# F405_MCU.net
KiCad netlist of a schematic drawn in Altium Designer
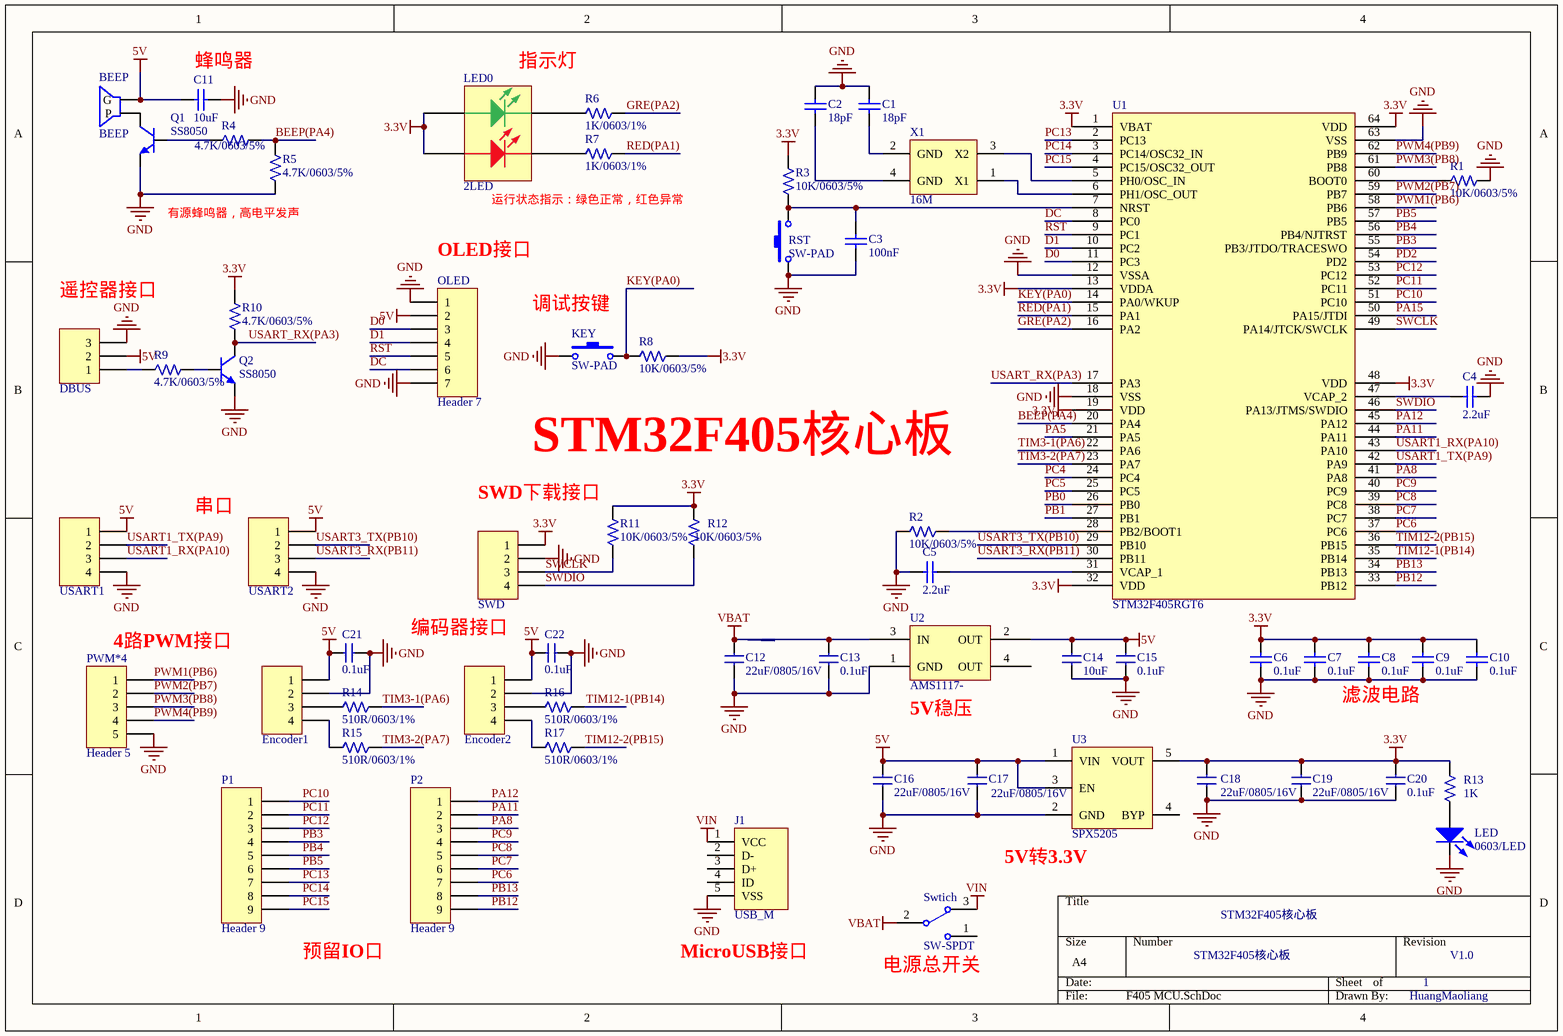
[diagram p0: F405 MCU.SchDoc]

(export (version "E")
  (design (tool "Eeschema 10.0.6"))
  (components
    (comp (ref "BEEP") (value "BEEP") (footprint "BELL-5") (libsource (lib "WARSHIP_SCH") (part "BEEP")))
    (comp (ref "C1")
      (value "18pF")
      (footprint "CAP-0603")
      (description "无极性电容")
      (fields (field (name "PUBLISHER") "Altium Limited"))
      (libsource (lib "My_Library") (part "Cap"))
    )
    (comp (ref "C2")
      (value "18pF")
      (footprint "CAP-0603")
      (description "无极性电容")
      (fields (field (name "PUBLISHER") "Altium Limited"))
      (libsource (lib "My_Library") (part "Cap"))
    )
    (comp (ref "C3")
      (value "100nF")
      (footprint "CAP-0603")
      (description "无极性电容")
      (fields (field (name "PUBLISHER") "Altium Limited"))
      (libsource (lib "My_Library") (part "Cap"))
    )
    (comp (ref "C4")
      (value "2.2uF")
      (footprint "CAP-0603")
      (description "无极性电容")
      (fields (field (name "PUBLISHER") "Altium Limited"))
      (libsource (lib "My_Library") (part "Cap"))
    )
    (comp (ref "C5")
      (value "2.2uF")
      (footprint "CAP-0603")
      (description "无极性电容")
      (fields (field (name "PUBLISHER") "Altium Limited"))
      (libsource (lib "My_Library") (part "Cap"))
    )
    (comp (ref "C6")
      (value "0.1uF")
      (footprint "CAP-0603")
      (description "无极性电容")
      (fields (field (name "PUBLISHER") "Altium Limited"))
      (libsource (lib "My_Library") (part "Cap"))
    )
    (comp (ref "C7")
      (value "0.1uF")
      (footprint "CAP-0603")
      (description "无极性电容")
      (fields (field (name "PUBLISHER") "Altium Limited"))
      (libsource (lib "My_Library") (part "Cap"))
    )
    (comp (ref "C8")
      (value "0.1uF")
      (footprint "CAP-0603")
      (description "无极性电容")
      (fields (field (name "PUBLISHER") "Altium Limited"))
      (libsource (lib "My_Library") (part "Cap"))
    )
    (comp (ref "C9")
      (value "0.1uF")
      (footprint "CAP-0603")
      (description "无极性电容")
      (fields (field (name "PUBLISHER") "Altium Limited"))
      (libsource (lib "My_Library") (part "Cap"))
    )
    (comp (ref "C10")
      (value "0.1uF")
      (footprint "CAP-0603")
      (description "无极性电容")
      (fields (field (name "PUBLISHER") "Altium Limited"))
      (libsource (lib "My_Library") (part "Cap"))
    )
    (comp (ref "C11")
      (value "10uF")
      (footprint "CAP-0603")
      (description "无极性电容")
      (fields (field (name "PUBLISHER") "Altium Limited"))
      (libsource (lib "My_Library") (part "Cap"))
    )
    (comp (ref "C12")
      (value "22uF/0805/16V")
      (footprint "0805")
      (libsource (lib "main control") (part "CAP/0805"))
    )
    (comp (ref "C13") (value "0.1uF") (footprint "0603") (libsource (lib "main control") (part "CAP/0603")))
    (comp (ref "C14") (value "10uF") (footprint "0603") (libsource (lib "main control") (part "CAP/0603")))
    (comp (ref "C15") (value "0.1uF") (footprint "0603") (libsource (lib "main control") (part "CAP/0603")))
    (comp (ref "C16")
      (value "22uF/0805/16V")
      (footprint "0805")
      (libsource (lib "main control") (part "CAP/0805"))
    )
    (comp (ref "C17")
      (value "22uF/0805/16V")
      (footprint "0805")
      (libsource (lib "main control") (part "CAP/0805"))
    )
    (comp (ref "C18")
      (value "22uF/0805/16V")
      (footprint "0805")
      (libsource (lib "main control") (part "CAP/0805"))
    )
    (comp (ref "C19")
      (value "22uF/0805/16V")
      (footprint "0805")
      (libsource (lib "main control") (part "CAP/0805"))
    )
    (comp (ref "C20") (value "0.1uF") (footprint "0603") (libsource (lib "main control") (part "CAP/0603")))
    (comp (ref "C21") (value "0.1uF") (footprint "0603") (libsource (lib "main control") (part "CAP/0603")))
    (comp (ref "C22") (value "0.1uF") (footprint "0603") (libsource (lib "main control") (part "CAP/0603")))
    (comp (ref "DBUS")
      (value "Header 3")
      (footprint "HDR3X1_A")
      (description "接插件")
      (fields (field (name "PUBLISHER") "Altium Limited"))
      (libsource (lib "Fszhang") (part "Header 3"))
    )
    (comp (ref "Encoder1")
      (value "Header 4")
      (footprint "HDR4X1_A")
      (description "接插件")
      (fields (field (name "PUBLISHER") "Altium Limited"))
      (libsource (lib "Fszhang") (part "Header 4"))
    )
    (comp (ref "Encoder2")
      (value "Header 4")
      (footprint "HDR4X1_A")
      (description "接插件")
      (fields (field (name "PUBLISHER") "Altium Limited"))
      (libsource (lib "Fszhang") (part "Header 4"))
    )
    (comp (ref "J1")
      (value "USB_M")
      (footprint "USB-MICRO")
      (description "MicroUSB接口")
      (libsource (lib "My_Library") (part "USB_M"))
    )
    (comp (ref "KEY")
      (value "SW-PAD")
      (footprint "SW_PAD1")
      (description "微动开关")
      (fields (field (name "PUBLISHER") "Altium Limited"))
      (libsource (lib "My_Library") (part "SW-PAD"))
    )
    (comp (ref "LED")
      (value "0603/LED")
      (footprint "0603")
      (libsource (lib "main control") (part "0603/LED"))
    )
    (comp (ref "LED0") (value "2LED") (footprint "LED-2-1206") (libsource (lib "main control") (part "2LED")))
    (comp (ref "OLED")
      (value "Header 7")
      (footprint "HDR1X7")
      (description "Header, 7-Pin")
      (fields (field (name "PUBLISHER") "Altium Limited"))
      (libsource (lib "Miscellaneous Connectors") (part "Header 7"))
    )
    (comp (ref "P1")
      (value "Header 9")
      (footprint "HDR1X9")
      (description "Header, 9-Pin")
      (fields (field (name "PUBLISHER") "Altium Limited"))
      (libsource (lib "Miscellaneous Connectors") (part "Header 9"))
    )
    (comp (ref "P2")
      (value "Header 9")
      (footprint "HDR1X9")
      (description "Header, 9-Pin")
      (fields (field (name "PUBLISHER") "Altium Limited"))
      (libsource (lib "Miscellaneous Connectors") (part "Header 9"))
    )
    (comp (ref "PWM*4")
      (value "Header 5")
      (footprint "HDR1X5")
      (description "Header, 5-Pin")
      (fields (field (name "PUBLISHER") "Altium Limited"))
      (libsource (lib "Miscellaneous Connectors") (part "Header 5"))
    )
    (comp (ref "Q1")
      (value "SS8050")
      (footprint "SOT-23")
      (description "NPN贴片三极管")
      (fields (field (name "PUBLISHER") "Altium Limited"))
      (libsource (lib "My_Library") (part "SS8050"))
    )
    (comp (ref "Q2")
      (value "SS8050")
      (footprint "SOT-23")
      (description "NPN贴片三极管")
      (fields (field (name "PUBLISHER") "Altium Limited"))
      (libsource (lib "My_Library") (part "SS8050"))
    )
    (comp (ref "R1")
      (value "10K/0603/5%")
      (footprint "0603")
      (libsource (lib "main control") (part "RES/0603"))
    )
    (comp (ref "R2")
      (value "10K/0603/5%")
      (footprint "0603")
      (libsource (lib "main control") (part "RES/0603"))
    )
    (comp (ref "R3")
      (value "10K/0603/5%")
      (footprint "0603")
      (libsource (lib "main control") (part "RES/0603"))
    )
    (comp (ref "R4")
      (value "4.7K/0603/5%")
      (footprint "0603")
      (libsource (lib "main control") (part "RES/0603"))
    )
    (comp (ref "R5")
      (value "4.7K/0603/5%")
      (footprint "0603")
      (libsource (lib "main control") (part "RES/0603"))
    )
    (comp (ref "R6")
      (value "1K/0603/1%")
      (footprint "0603")
      (libsource (lib "main control") (part "RES/0603"))
    )
    (comp (ref "R7")
      (value "1K/0603/1%")
      (footprint "0603")
      (libsource (lib "main control") (part "RES/0603"))
    )
    (comp (ref "R8")
      (value "10K/0603/5%")
      (footprint "0603")
      (libsource (lib "main control") (part "RES/0603"))
    )
    (comp (ref "R9")
      (value "4.7K/0603/5%")
      (footprint "0603")
      (libsource (lib "main control") (part "RES/0603"))
    )
    (comp (ref "R10")
      (value "4.7K/0603/5%")
      (footprint "0603")
      (libsource (lib "main control") (part "RES/0603"))
    )
    (comp (ref "R11")
      (value "10K/0603/5%")
      (footprint "0603")
      (libsource (lib "main control") (part "RES/0603"))
    )
    (comp (ref "R12")
      (value "10K/0603/5%")
      (footprint "0603")
      (libsource (lib "main control") (part "RES/0603"))
    )
    (comp (ref "R13") (value "1K") (footprint "0603") (libsource (lib "main control") (part "RES/0603")))
    (comp (ref "R14")
      (value "510R/0603/1%")
      (footprint "0603")
      (libsource (lib "main control") (part "RES/0603"))
    )
    (comp (ref "R15")
      (value "510R/0603/1%")
      (footprint "0603")
      (libsource (lib "main control") (part "RES/0603"))
    )
    (comp (ref "R16")
      (value "510R/0603/1%")
      (footprint "0603")
      (libsource (lib "main control") (part "RES/0603"))
    )
    (comp (ref "R17")
      (value "510R/0603/1%")
      (footprint "0603")
      (libsource (lib "main control") (part "RES/0603"))
    )
    (comp (ref "RST")
      (value "SW-PAD")
      (footprint "SW_PAD1")
      (description "微动开关")
      (fields (field (name "PUBLISHER") "Altium Limited"))
      (libsource (lib "My_Library") (part "SW-PAD"))
    )
    (comp (ref "SWD")
      (value "Header 4")
      (footprint "HDR4X1_A")
      (description "接插件")
      (fields (field (name "PUBLISHER") "Altium Limited"))
      (libsource (lib "Fszhang") (part "Header 4"))
    )
    (comp (ref "Swtich")
      (value "SW-SPDT")
      (footprint "MSK-12D19")
      (description "开关")
      (fields (field (name "PUBLISHER") "Altium Limited"))
      (libsource (lib "My_Library") (part "SW-SPDT"))
    )
    (comp (ref "U1")
      (value "STM32F405RGT6")
      (footprint "STM32F405RGT6 - duplicate")
      (libsource (lib "My Integrated_Library") (part "STM32F405RGT6"))
    )
    (comp (ref "U2")
      (value "AMS1117-")
      (footprint "SOT-89-3")
      (description "稳压芯片")
      (libsource (lib "My_Library") (part "AMS1117"))
    )
    (comp (ref "U3")
      (value "SPX5205")
      (footprint "SPX5205M5-3.3V")
      (description "5转3.3V LDO")
      (libsource (lib "My_Library") (part "SPX5205M5-3.3V"))
    )
    (comp (ref "USART1")
      (value "Header 4")
      (footprint "HDR4X1_A")
      (description "接插件")
      (fields (field (name "PUBLISHER") "Altium Limited"))
      (libsource (lib "Fszhang") (part "Header 4"))
    )
    (comp (ref "USART2")
      (value "Header 4")
      (footprint "HDR4X1_A")
      (description "接插件")
      (fields (field (name "PUBLISHER") "Altium Limited"))
      (libsource (lib "Fszhang") (part "Header 4"))
    )
    (comp (ref "X1")
      (value "16M")
      (footprint "X-3225")
      (description "贴片晶振")
      (libsource (lib "My_Library") (part "XTAL-M"))
    )
  )
  (nets
    (net (code "1") (name "/BEEP(PA4)") (class "Default")
      (node (ref "R4") (pin "1") (pinfunction "1_1") (pintype "passive"))
      (node (ref "R5") (pin "1") (pinfunction "1_1") (pintype "passive"))
      (node (ref "U1") (pin "20") (pinfunction "PA4_20") (pintype "passive"))
    )
    (net (code "2") (name "/D0") (class "Default")
      (node (ref "OLED") (pin "3") (pinfunction "3_3") (pintype "passive"))
      (node (ref "U1") (pin "11") (pinfunction "PC3_11") (pintype "passive"))
    )
    (net (code "3") (name "/D1") (class "Default")
      (node (ref "OLED") (pin "4") (pinfunction "4_4") (pintype "passive"))
      (node (ref "U1") (pin "10") (pinfunction "PC2_10") (pintype "passive"))
    )
    (net (code "4") (name "/DC") (class "Default")
      (node (ref "OLED") (pin "6") (pinfunction "6_6") (pintype "passive"))
      (node (ref "U1") (pin "8") (pinfunction "PC0_8") (pintype "passive"))
    )
    (net (code "5") (name "/GRE(PA2)") (class "Default")
      (node (ref "R6") (pin "2") (pinfunction "2_2") (pintype "passive"))
      (node (ref "U1") (pin "16") (pinfunction "PA2_16") (pintype "passive"))
    )
    (net (code "6") (name "/KEY(PA0)") (class "Default")
      (node (ref "KEY") (pin "2") (pinfunction "2_2") (pintype "passive"))
      (node (ref "R8") (pin "1") (pinfunction "1_1") (pintype "passive"))
      (node (ref "U1") (pin "14") (pinfunction "PA0/WKUP_14") (pintype "passive"))
    )
    (net (code "7") (name "/PA5") (class "Default")
      (node (ref "U1") (pin "21") (pinfunction "PA5_21") (pintype "passive"))
    )
    (net (code "8") (name "/PA8") (class "Default")
      (node (ref "P2") (pin "3") (pinfunction "3_3") (pintype "passive"))
      (node (ref "U1") (pin "41") (pinfunction "PA8_41") (pintype "passive"))
    )
    (net (code "9") (name "/PA11") (class "Default")
      (node (ref "P2") (pin "2") (pinfunction "2_2") (pintype "passive"))
      (node (ref "U1") (pin "44") (pinfunction "PA11_44") (pintype "passive"))
    )
    (net (code "10") (name "/PA12") (class "Default")
      (node (ref "P2") (pin "1") (pinfunction "1_1") (pintype "passive"))
      (node (ref "U1") (pin "45") (pinfunction "PA12_45") (pintype "passive"))
    )
    (net (code "11") (name "/PA15") (class "Default")
      (node (ref "U1") (pin "50") (pinfunction "PA15/JTDI_50") (pintype "passive"))
    )
    (net (code "12") (name "/PB0") (class "Default")
      (node (ref "U1") (pin "26") (pinfunction "PB0_26") (pintype "passive"))
    )
    (net (code "13") (name "/PB1") (class "Default")
      (node (ref "U1") (pin "27") (pinfunction "PB1_27") (pintype "passive"))
    )
    (net (code "14") (name "/PB3") (class "Default")
      (node (ref "P1") (pin "4") (pinfunction "4_4") (pintype "passive"))
      (node (ref "U1") (pin "55") (pinfunction "PB3/JTDO/TRACESWO_55") (pintype "passive"))
    )
    (net (code "15") (name "/PB4") (class "Default")
      (node (ref "P1") (pin "5") (pinfunction "5_5") (pintype "passive"))
      (node (ref "U1") (pin "56") (pinfunction "PB4/NJTRST_56") (pintype "passive"))
    )
    (net (code "16") (name "/PB5") (class "Default")
      (node (ref "P1") (pin "6") (pinfunction "6_6") (pintype "passive"))
      (node (ref "U1") (pin "57") (pinfunction "PB5_57") (pintype "passive"))
    )
    (net (code "17") (name "/PB12") (class "Default")
      (node (ref "P2") (pin "9") (pinfunction "9_9") (pintype "passive"))
      (node (ref "U1") (pin "33") (pinfunction "PB12_33") (pintype "passive"))
    )
    (net (code "18") (name "/PB13") (class "Default")
      (node (ref "P2") (pin "8") (pinfunction "8_8") (pintype "passive"))
      (node (ref "U1") (pin "34") (pinfunction "PB13_34") (pintype "passive"))
    )
    (net (code "19") (name "/PC4") (class "Default")
      (node (ref "U1") (pin "24") (pinfunction "PC4_24") (pintype "passive"))
    )
    (net (code "20") (name "/PC5") (class "Default")
      (node (ref "U1") (pin "25") (pinfunction "PC5_25") (pintype "passive"))
    )
    (net (code "21") (name "/PC6") (class "Default")
      (node (ref "P2") (pin "7") (pinfunction "7_7") (pintype "passive"))
      (node (ref "U1") (pin "37") (pinfunction "PC6_37") (pintype "passive"))
    )
    (net (code "22") (name "/PC7") (class "Default")
      (node (ref "P2") (pin "6") (pinfunction "6_6") (pintype "passive"))
      (node (ref "U1") (pin "38") (pinfunction "PC7_38") (pintype "passive"))
    )
    (net (code "23") (name "/PC8") (class "Default")
      (node (ref "P2") (pin "5") (pinfunction "5_5") (pintype "passive"))
      (node (ref "U1") (pin "39") (pinfunction "PC8_39") (pintype "passive"))
    )
    (net (code "24") (name "/PC9") (class "Default")
      (node (ref "P2") (pin "4") (pinfunction "4_4") (pintype "passive"))
      (node (ref "U1") (pin "40") (pinfunction "PC9_40") (pintype "passive"))
    )
    (net (code "25") (name "/PC10") (class "Default")
      (node (ref "P1") (pin "1") (pinfunction "1_1") (pintype "passive"))
      (node (ref "U1") (pin "51") (pinfunction "PC10_51") (pintype "passive"))
    )
    (net (code "26") (name "/PC11") (class "Default")
      (node (ref "P1") (pin "2") (pinfunction "2_2") (pintype "passive"))
      (node (ref "U1") (pin "52") (pinfunction "PC11_52") (pintype "passive"))
    )
    (net (code "27") (name "/PC12") (class "Default")
      (node (ref "P1") (pin "3") (pinfunction "3_3") (pintype "passive"))
      (node (ref "U1") (pin "53") (pinfunction "PC12_53") (pintype "passive"))
    )
    (net (code "28") (name "/PC13") (class "Default")
      (node (ref "P1") (pin "7") (pinfunction "7_7") (pintype "passive"))
      (node (ref "U1") (pin "2") (pinfunction "PC13_2") (pintype "passive"))
    )
    (net (code "29") (name "/PC14") (class "Default")
      (node (ref "P1") (pin "8") (pinfunction "8_8") (pintype "passive"))
      (node (ref "U1") (pin "3") (pinfunction "PC14/OSC32_IN_3") (pintype "passive"))
    )
    (net (code "30") (name "/PC15") (class "Default")
      (node (ref "P1") (pin "9") (pinfunction "9_9") (pintype "passive"))
      (node (ref "U1") (pin "4") (pinfunction "PC15/OSC32_OUT_4") (pintype "passive"))
    )
    (net (code "31") (name "/PD2") (class "Default")
      (node (ref "U1") (pin "54") (pinfunction "PD2_54") (pintype "passive"))
    )
    (net (code "32") (name "/PWM1(PB6)") (class "Default")
      (node (ref "PWM*4") (pin "1") (pinfunction "1_1") (pintype "passive"))
      (node (ref "U1") (pin "58") (pinfunction "PB6_58") (pintype "passive"))
    )
    (net (code "33") (name "/PWM2(PB7)") (class "Default")
      (node (ref "PWM*4") (pin "2") (pinfunction "2_2") (pintype "passive"))
      (node (ref "U1") (pin "59") (pinfunction "PB7_59") (pintype "passive"))
    )
    (net (code "34") (name "/PWM3(PB8)") (class "Default")
      (node (ref "PWM*4") (pin "3") (pinfunction "3_3") (pintype "passive"))
      (node (ref "U1") (pin "61") (pinfunction "PB8_61") (pintype "passive"))
    )
    (net (code "35") (name "/PWM4(PB9)") (class "Default")
      (node (ref "PWM*4") (pin "4") (pinfunction "4_4") (pintype "passive"))
      (node (ref "U1") (pin "62") (pinfunction "PB9_62") (pintype "passive"))
    )
    (net (code "36") (name "/RED(PA1)") (class "Default")
      (node (ref "R7") (pin "2") (pinfunction "2_2") (pintype "passive"))
      (node (ref "U1") (pin "15") (pinfunction "PA1_15") (pintype "passive"))
    )
    (net (code "37") (name "/RST") (class "Default")
      (node (ref "OLED") (pin "5") (pinfunction "5_5") (pintype "passive"))
      (node (ref "U1") (pin "9") (pinfunction "PC1_9") (pintype "passive"))
    )
    (net (code "38") (name "/SWCLK") (class "Default")
      (node (ref "R11") (pin "1") (pinfunction "1_1") (pintype "passive"))
      (node (ref "SWD") (pin "3") (pinfunction "3_3") (pintype "passive"))
      (node (ref "U1") (pin "49") (pinfunction "PA14/JTCK/SWCLK_49") (pintype "passive"))
    )
    (net (code "39") (name "/SWDIO") (class "Default")
      (node (ref "R12") (pin "1") (pinfunction "1_1") (pintype "passive"))
      (node (ref "SWD") (pin "4") (pinfunction "4_4") (pintype "passive"))
      (node (ref "U1") (pin "46") (pinfunction "PA13/JTMS/SWDIO_46") (pintype "passive"))
    )
    (net (code "40") (name "/TIM3-1(PA6)") (class "Default")
      (node (ref "R14") (pin "2") (pinfunction "2_2") (pintype "passive"))
      (node (ref "U1") (pin "22") (pinfunction "PA6_22") (pintype "passive"))
    )
    (net (code "41") (name "/TIM3-2(PA7)") (class "Default")
      (node (ref "R15") (pin "2") (pinfunction "2_2") (pintype "passive"))
      (node (ref "U1") (pin "23") (pinfunction "PA7_23") (pintype "passive"))
    )
    (net (code "42") (name "/TIM12-1(PB14)") (class "Default")
      (node (ref "R16") (pin "2") (pinfunction "2_2") (pintype "passive"))
      (node (ref "U1") (pin "35") (pinfunction "PB14_35") (pintype "passive"))
    )
    (net (code "43") (name "/TIM12-2(PB15)") (class "Default")
      (node (ref "R17") (pin "2") (pinfunction "2_2") (pintype "passive"))
      (node (ref "U1") (pin "36") (pinfunction "PB15_36") (pintype "passive"))
    )
    (net (code "44") (name "/USART1_RX(PA10)") (class "Default")
      (node (ref "U1") (pin "43") (pinfunction "PA10_43") (pintype "passive"))
      (node (ref "USART1") (pin "3") (pinfunction "3_3") (pintype "passive"))
    )
    (net (code "45") (name "/USART1_TX(PA9)") (class "Default")
      (node (ref "U1") (pin "42") (pinfunction "PA9_42") (pintype "passive"))
      (node (ref "USART1") (pin "2") (pinfunction "2_2") (pintype "passive"))
    )
    (net (code "46") (name "/USART3_RX(PB11)") (class "Default")
      (node (ref "U1") (pin "30") (pinfunction "PB11_30") (pintype "passive"))
      (node (ref "USART2") (pin "3") (pinfunction "3_3") (pintype "passive"))
    )
    (net (code "47") (name "/USART3_TX(PB10)") (class "Default")
      (node (ref "U1") (pin "29") (pinfunction "PB10_29") (pintype "passive"))
      (node (ref "USART2") (pin "2") (pinfunction "2_2") (pintype "passive"))
    )
    (net (code "48") (name "/USART_RX(PA3)") (class "Default")
      (node (ref "Q2") (pin "3") (pinfunction "C_3") (pintype "passive"))
      (node (ref "R10") (pin "1") (pinfunction "1_1") (pintype "passive"))
      (node (ref "U1") (pin "17") (pinfunction "PA3_17") (pintype "passive"))
    )
    (net (code "49") (name "3.3V") (class "Default")
      (node (ref "C10") (pin "2") (pinfunction "2_2") (pintype "passive"))
      (node (ref "C18") (pin "2") (pinfunction "2_2") (pintype "passive"))
      (node (ref "C19") (pin "2") (pinfunction "2_2") (pintype "passive"))
      (node (ref "C20") (pin "2") (pinfunction "2_2") (pintype "passive"))
      (node (ref "C6") (pin "2") (pinfunction "2_2") (pintype "passive"))
      (node (ref "C7") (pin "2") (pinfunction "2_2") (pintype "passive"))
      (node (ref "C8") (pin "2") (pinfunction "2_2") (pintype "passive"))
      (node (ref "C9") (pin "2") (pinfunction "2_2") (pintype "passive"))
      (node (ref "LED0") (pin "1") (pinfunction "1_1") (pintype "passive"))
      (node (ref "LED0") (pin "2") (pinfunction "2_2") (pintype "passive"))
      (node (ref "R10") (pin "2") (pinfunction "2_2") (pintype "passive"))
      (node (ref "R11") (pin "2") (pinfunction "2_2") (pintype "passive"))
      (node (ref "R12") (pin "2") (pinfunction "2_2") (pintype "passive"))
      (node (ref "R13") (pin "2") (pinfunction "2_2") (pintype "passive"))
      (node (ref "R3") (pin "2") (pinfunction "2_2") (pintype "passive"))
      (node (ref "R8") (pin "2") (pinfunction "2_2") (pintype "passive"))
      (node (ref "SWD") (pin "1") (pinfunction "1_1") (pintype "passive"))
      (node (ref "U1") (pin "1") (pinfunction "VBAT_1") (pintype "passive"))
      (node (ref "U1") (pin "13") (pinfunction "VDDA_13") (pintype "passive"))
      (node (ref "U1") (pin "19") (pinfunction "VDD_19") (pintype "passive"))
      (node (ref "U1") (pin "32") (pinfunction "VDD_32") (pintype "passive"))
      (node (ref "U1") (pin "48") (pinfunction "VDD_48") (pintype "passive"))
      (node (ref "U1") (pin "64") (pinfunction "VDD_64") (pintype "passive"))
      (node (ref "U3") (pin "5") (pinfunction "VOUT_5") (pintype "passive"))
    )
    (net (code "50") (name "5V") (class "Default")
      (node (ref "BEEP") (pin "2") (pinfunction "G_2") (pintype "passive"))
      (node (ref "C11") (pin "1") (pinfunction "1_1") (pintype "passive"))
      (node (ref "C14") (pin "2") (pinfunction "2_2") (pintype "passive"))
      (node (ref "C15") (pin "2") (pinfunction "2_2") (pintype "passive"))
      (node (ref "C16") (pin "2") (pinfunction "2_2") (pintype "passive"))
      (node (ref "C17") (pin "2") (pinfunction "2_2") (pintype "passive"))
      (node (ref "C21") (pin "2") (pinfunction "2_2") (pintype "passive"))
      (node (ref "C22") (pin "1") (pinfunction "1_1") (pintype "passive"))
      (node (ref "DBUS") (pin "2") (pinfunction "2_2") (pintype "passive"))
      (node (ref "Encoder1") (pin "1") (pinfunction "1_1") (pintype "passive"))
      (node (ref "Encoder2") (pin "1") (pinfunction "1_1") (pintype "passive"))
      (node (ref "OLED") (pin "2") (pinfunction "2_2") (pintype "passive"))
      (node (ref "U2") (pin "2") (pinfunction "OUT_2") (pintype "passive"))
      (node (ref "U3") (pin "1") (pinfunction "VIN_1") (pintype "passive"))
      (node (ref "U3") (pin "3") (pinfunction "EN_3") (pintype "passive"))
      (node (ref "USART1") (pin "1") (pinfunction "1_1") (pintype "passive"))
      (node (ref "USART2") (pin "1") (pinfunction "1_1") (pintype "passive"))
    )
    (net (code "51") (name "GND") (class "Default")
      (node (ref "C1") (pin "2") (pinfunction "2_2") (pintype "passive"))
      (node (ref "C10") (pin "1") (pinfunction "1_1") (pintype "passive"))
      (node (ref "C11") (pin "2") (pinfunction "2_2") (pintype "passive"))
      (node (ref "C12") (pin "1") (pinfunction "1_1") (pintype "passive"))
      (node (ref "C13") (pin "1") (pinfunction "1_1") (pintype "passive"))
      (node (ref "C14") (pin "1") (pinfunction "1_1") (pintype "passive"))
      (node (ref "C15") (pin "1") (pinfunction "1_1") (pintype "passive"))
      (node (ref "C16") (pin "1") (pinfunction "1_1") (pintype "passive"))
      (node (ref "C17") (pin "1") (pinfunction "1_1") (pintype "passive"))
      (node (ref "C18") (pin "1") (pinfunction "1_1") (pintype "passive"))
      (node (ref "C19") (pin "1") (pinfunction "1_1") (pintype "passive"))
      (node (ref "C2") (pin "2") (pinfunction "2_2") (pintype "passive"))
      (node (ref "C20") (pin "1") (pinfunction "1_1") (pintype "passive"))
      (node (ref "C21") (pin "1") (pinfunction "1_1") (pintype "passive"))
      (node (ref "C22") (pin "2") (pinfunction "2_2") (pintype "passive"))
      (node (ref "C3") (pin "1") (pinfunction "1_1") (pintype "passive"))
      (node (ref "C4") (pin "1") (pinfunction "1_1") (pintype "passive"))
      (node (ref "C5") (pin "2") (pinfunction "2_2") (pintype "passive"))
      (node (ref "C6") (pin "1") (pinfunction "1_1") (pintype "passive"))
      (node (ref "C7") (pin "1") (pinfunction "1_1") (pintype "passive"))
      (node (ref "C8") (pin "1") (pinfunction "1_1") (pintype "passive"))
      (node (ref "C9") (pin "1") (pinfunction "1_1") (pintype "passive"))
      (node (ref "DBUS") (pin "3") (pinfunction "3_3") (pintype "passive"))
      (node (ref "Encoder1") (pin "2") (pinfunction "2_2") (pintype "passive"))
      (node (ref "Encoder2") (pin "2") (pinfunction "2_2") (pintype "passive"))
      (node (ref "J1") (pin "5") (pinfunction "VSS_5") (pintype "passive"))
      (node (ref "KEY") (pin "1") (pinfunction "1_1") (pintype "passive"))
      (node (ref "LED") (pin "2") (pinfunction "K_2") (pintype "passive"))
      (node (ref "OLED") (pin "1") (pinfunction "1_1") (pintype "passive"))
      (node (ref "OLED") (pin "7") (pinfunction "7_7") (pintype "passive"))
      (node (ref "PWM*4") (pin "5") (pinfunction "5_5") (pintype "passive"))
      (node (ref "Q1") (pin "2") (pinfunction "E_2") (pintype "passive"))
      (node (ref "Q2") (pin "2") (pinfunction "E_2") (pintype "passive"))
      (node (ref "R1") (pin "2") (pinfunction "2_2") (pintype "passive"))
      (node (ref "R2") (pin "1") (pinfunction "1_1") (pintype "passive"))
      (node (ref "R5") (pin "2") (pinfunction "2_2") (pintype "passive"))
      (node (ref "RST") (pin "1") (pinfunction "1_1") (pintype "passive"))
      (node (ref "SWD") (pin "2") (pinfunction "2_2") (pintype "passive"))
      (node (ref "U1") (pin "12") (pinfunction "VSSA_12") (pintype "passive"))
      (node (ref "U1") (pin "18") (pinfunction "VSS_18") (pintype "passive"))
      (node (ref "U1") (pin "63") (pinfunction "VSS_63") (pintype "passive"))
      (node (ref "U2") (pin "1") (pinfunction "GND_1") (pintype "passive"))
      (node (ref "U3") (pin "2") (pinfunction "GND_2") (pintype "passive"))
      (node (ref "USART1") (pin "4") (pinfunction "4_4") (pintype "passive"))
      (node (ref "USART2") (pin "4") (pinfunction "4_4") (pintype "passive"))
    )
    (net (code "52") (name "Net-(BEEP-P)") (class "Default")
      (node (ref "BEEP") (pin "1") (pinfunction "P_1") (pintype "passive"))
      (node (ref "Q1") (pin "3") (pinfunction "C_3") (pintype "passive"))
    )
    (net (code "53") (name "Net-(C1-Pad1)") (class "Default")
      (node (ref "C1") (pin "1") (pinfunction "1_1") (pintype "passive"))
      (node (ref "X1") (pin "2") (pinfunction "GND_2") (pintype "passive"))
    )
    (net (code "54") (name "Net-(C2-Pad1)") (class "Default")
      (node (ref "C2") (pin "1") (pinfunction "1_1") (pintype "passive"))
      (node (ref "X1") (pin "4") (pinfunction "GND_4") (pintype "passive"))
    )
    (net (code "55") (name "Net-(DBUS-Pad1)") (class "Default")
      (node (ref "DBUS") (pin "1") (pinfunction "1_1") (pintype "passive"))
      (node (ref "R9") (pin "1") (pinfunction "1_1") (pintype "passive"))
    )
    (net (code "56") (name "Net-(Encoder1-Pad3)") (class "Default")
      (node (ref "Encoder1") (pin "3") (pinfunction "3_3") (pintype "passive"))
      (node (ref "R14") (pin "1") (pinfunction "1_1") (pintype "passive"))
    )
    (net (code "57") (name "Net-(Encoder1-Pad4)") (class "Default")
      (node (ref "Encoder1") (pin "4") (pinfunction "4_4") (pintype "passive"))
      (node (ref "R15") (pin "1") (pinfunction "1_1") (pintype "passive"))
    )
    (net (code "58") (name "Net-(Encoder2-Pad3)") (class "Default")
      (node (ref "Encoder2") (pin "3") (pinfunction "3_3") (pintype "passive"))
      (node (ref "R16") (pin "1") (pinfunction "1_1") (pintype "passive"))
    )
    (net (code "59") (name "Net-(Encoder2-Pad4)") (class "Default")
      (node (ref "Encoder2") (pin "4") (pinfunction "4_4") (pintype "passive"))
      (node (ref "R17") (pin "1") (pinfunction "1_1") (pintype "passive"))
    )
    (net (code "60") (name "Net-(LED-A)") (class "Default")
      (node (ref "LED") (pin "1") (pinfunction "A_1") (pintype "passive"))
      (node (ref "R13") (pin "1") (pinfunction "1_1") (pintype "passive"))
    )
    (net (code "61") (name "Net-(LED0-Pad3)") (class "Default")
      (node (ref "LED0") (pin "3") (pinfunction "3_3") (pintype "passive"))
      (node (ref "R6") (pin "1") (pinfunction "1_1") (pintype "passive"))
    )
    (net (code "62") (name "Net-(LED0-Pad4)") (class "Default")
      (node (ref "LED0") (pin "4") (pinfunction "4_4") (pintype "passive"))
      (node (ref "R7") (pin "1") (pinfunction "1_1") (pintype "passive"))
    )
    (net (code "63") (name "Net-(Q1-B)") (class "Default")
      (node (ref "Q1") (pin "1") (pinfunction "B_1") (pintype "passive"))
      (node (ref "R4") (pin "2") (pinfunction "2_2") (pintype "passive"))
    )
    (net (code "64") (name "Net-(Q2-B)") (class "Default")
      (node (ref "Q2") (pin "1") (pinfunction "B_1") (pintype "passive"))
      (node (ref "R9") (pin "2") (pinfunction "2_2") (pintype "passive"))
    )
    (net (code "65") (name "Net-(U1-BOOT0)") (class "Default")
      (node (ref "R1") (pin "1") (pinfunction "1_1") (pintype "passive"))
      (node (ref "U1") (pin "60") (pinfunction "BOOT0_60") (pintype "passive"))
    )
    (net (code "66") (name "Net-(U1-NRST)") (class "Default")
      (node (ref "C3") (pin "2") (pinfunction "2_2") (pintype "passive"))
      (node (ref "R3") (pin "1") (pinfunction "1_1") (pintype "passive"))
      (node (ref "RST") (pin "2") (pinfunction "2_2") (pintype "passive"))
      (node (ref "U1") (pin "7") (pinfunction "NRST_7") (pintype "passive"))
    )
    (net (code "67") (name "Net-(U1-PB2{slash}BOOT1)") (class "Default")
      (node (ref "R2") (pin "2") (pinfunction "2_2") (pintype "passive"))
      (node (ref "U1") (pin "28") (pinfunction "PB2/BOOT1_28") (pintype "passive"))
    )
    (net (code "68") (name "Net-(U1-PH0{slash}OSC_IN)") (class "Default")
      (node (ref "U1") (pin "5") (pinfunction "PH0/OSC_IN_5") (pintype "passive"))
      (node (ref "X1") (pin "3") (pinfunction "X2_3") (pintype "passive"))
    )
    (net (code "69") (name "Net-(U1-PH1{slash}OSC_OUT)") (class "Default")
      (node (ref "U1") (pin "6") (pinfunction "PH1/OSC_OUT_6") (pintype "passive"))
      (node (ref "X1") (pin "1") (pinfunction "X1_1") (pintype "passive"))
    )
    (net (code "70") (name "Net-(U1-VCAP_1)") (class "Default")
      (node (ref "C5") (pin "1") (pinfunction "1_1") (pintype "passive"))
      (node (ref "U1") (pin "31") (pinfunction "VCAP_1_31") (pintype "passive"))
    )
    (net (code "71") (name "Net-(U1-VCAP_2)") (class "Default")
      (node (ref "C4") (pin "2") (pinfunction "2_2") (pintype "passive"))
      (node (ref "U1") (pin "47") (pinfunction "VCAP_2_47") (pintype "passive"))
    )
    (net (code "72") (name "VBAT") (class "Default")
      (node (ref "C12") (pin "2") (pinfunction "2_2") (pintype "passive"))
      (node (ref "C13") (pin "2") (pinfunction "2_2") (pintype "passive"))
      (node (ref "Swtich") (pin "2") (pinfunction "2_2") (pintype "passive"))
      (node (ref "U2") (pin "3") (pinfunction "IN_3") (pintype "passive"))
    )
    (net (code "73") (name "VIN") (class "Default")
      (node (ref "J1") (pin "1") (pinfunction "VCC_1") (pintype "passive"))
      (node (ref "Swtich") (pin "3") (pinfunction "3_3") (pintype "passive"))
    )
    (net (code "74") (name "unconnected-(J1-D+-Pad3)") (class "Default")
      (node (ref "J1") (pin "3") (pinfunction "D+_3") (pintype "passive"))
    )
    (net (code "75") (name "unconnected-(J1-D--Pad2)") (class "Default")
      (node (ref "J1") (pin "2") (pinfunction "D-_2") (pintype "passive"))
    )
    (net (code "76") (name "unconnected-(J1-ID-Pad4)") (class "Default")
      (node (ref "J1") (pin "4") (pinfunction "ID_4") (pintype "passive"))
    )
    (net (code "77") (name "unconnected-(Swtich-Pad1)") (class "Default")
      (node (ref "Swtich") (pin "1") (pinfunction "1_1") (pintype "passive"))
    )
    (net (code "78") (name "unconnected-(U2-OUT-Pad4)") (class "Default")
      (node (ref "U2") (pin "4") (pinfunction "OUT_4") (pintype "passive"))
    )
    (net (code "79") (name "unconnected-(U3-BYP-Pad4)") (class "Default")
      (node (ref "U3") (pin "4") (pinfunction "BYP_4") (pintype "passive"))
    )
  )
)
